# TurboMaster-clean.net
KiCad netlist of a schematic drawn in EAGLE
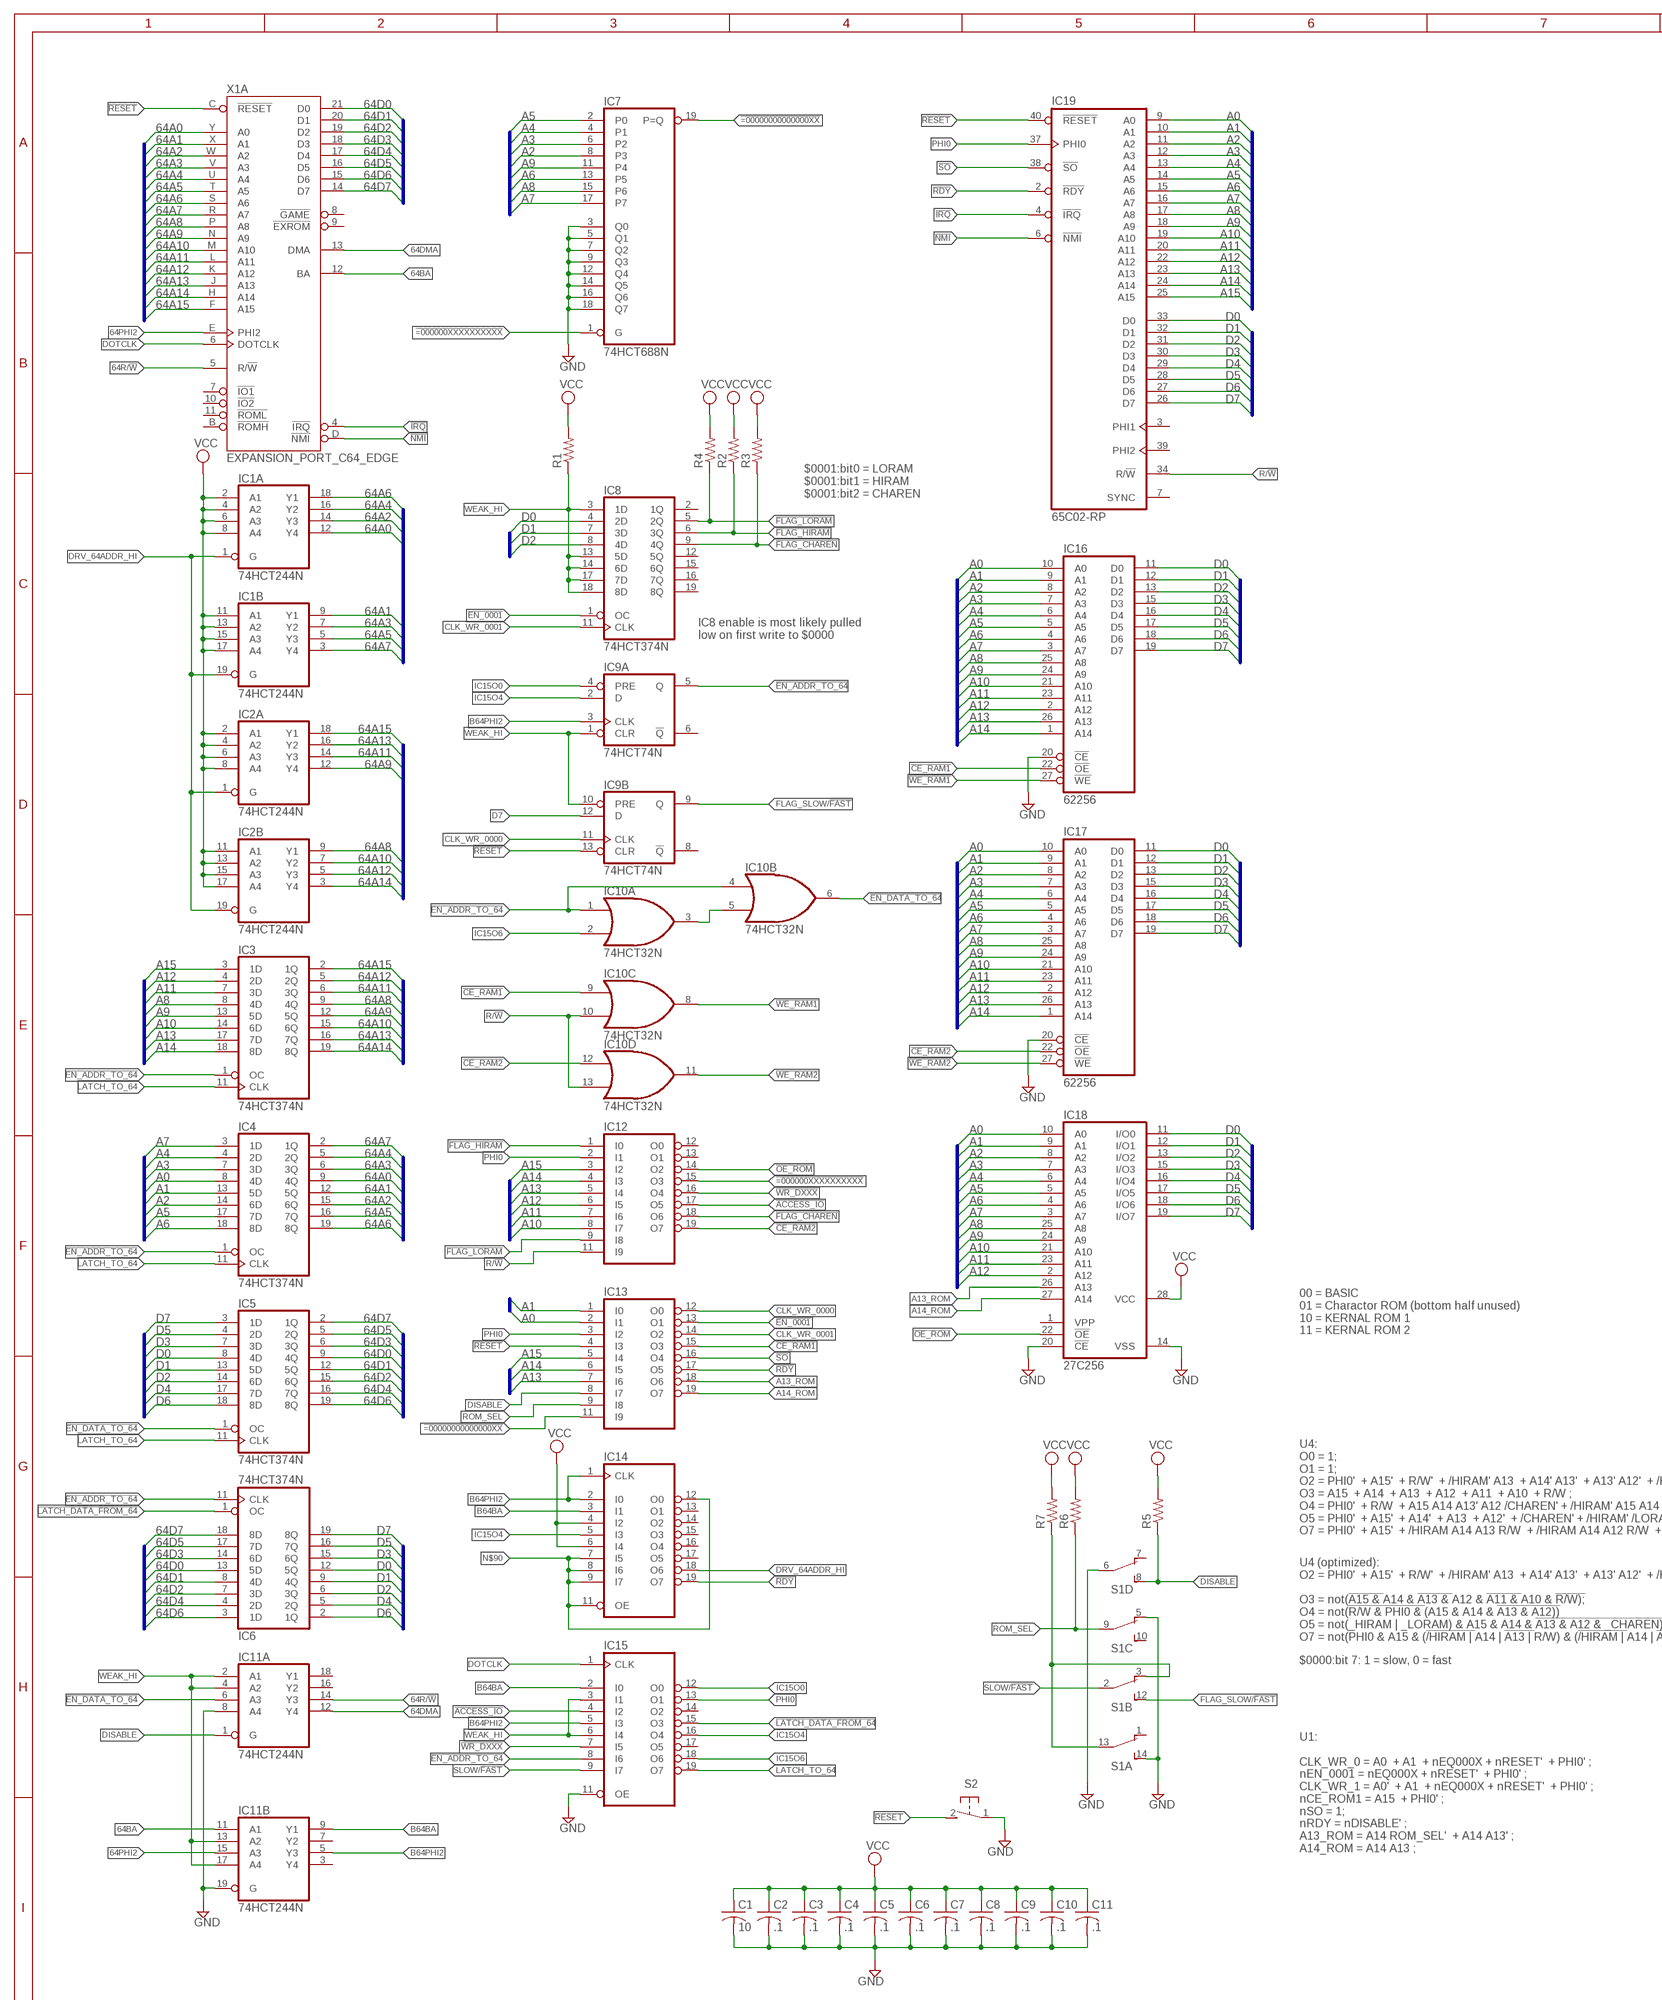
[diagram p0: schematic, sheet 1, part 1 of 2]
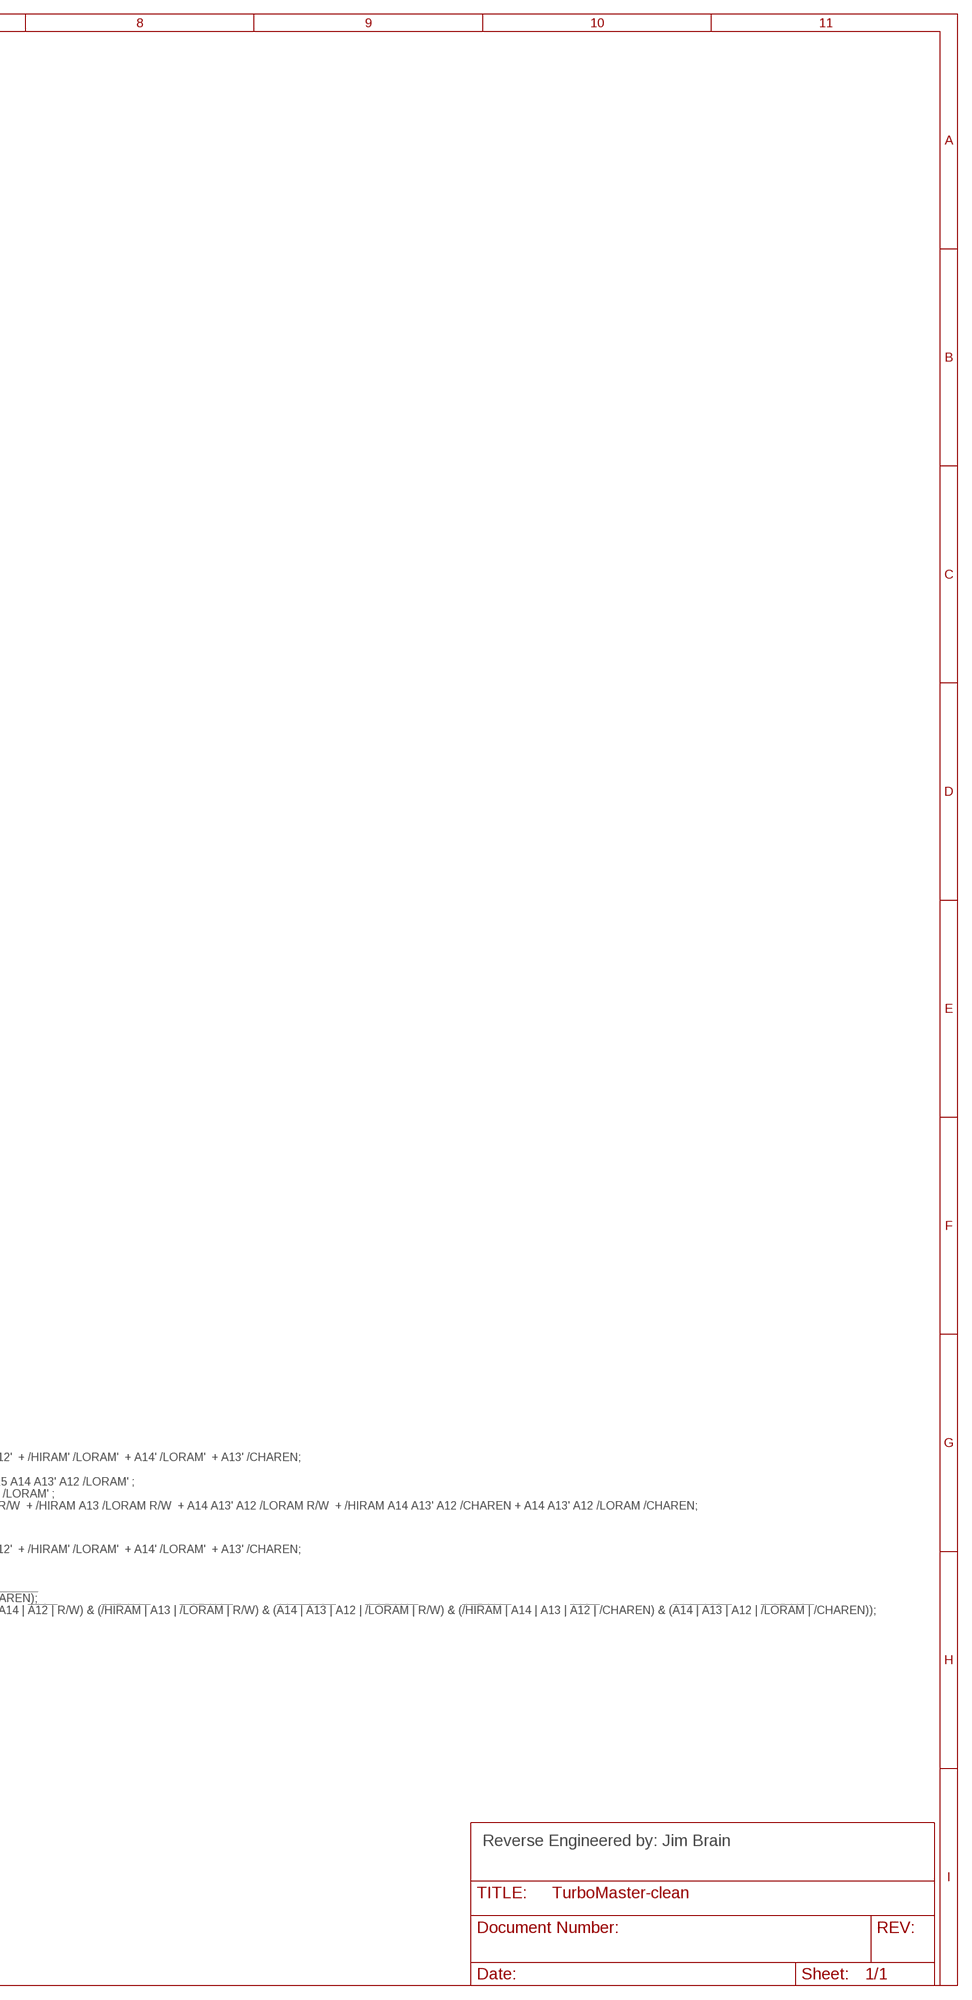
[diagram p1: schematic, sheet 1, part 2 of 2]

(export (version "E")
  (design (tool "Eeschema 10.0.6"))
  (components
    (comp (ref "C1")
      (value "10")
      (footprint "eagle-import:C050-024X044")
      (libsource (lib "eagle-import") (part "C-US050-024X044"))
    )
    (comp (ref "C2")
      (value ".1")
      (footprint "eagle-import:C050-024X044")
      (libsource (lib "eagle-import") (part "C-US050-024X044"))
    )
    (comp (ref "C3")
      (value ".1")
      (footprint "eagle-import:C050-024X044")
      (libsource (lib "eagle-import") (part "C-US050-024X044"))
    )
    (comp (ref "C4")
      (value ".1")
      (footprint "eagle-import:C050-024X044")
      (libsource (lib "eagle-import") (part "C-US050-024X044"))
    )
    (comp (ref "C5")
      (value ".1")
      (footprint "eagle-import:C050-024X044")
      (libsource (lib "eagle-import") (part "C-US050-024X044"))
    )
    (comp (ref "C6")
      (value ".1")
      (footprint "eagle-import:C050-024X044")
      (libsource (lib "eagle-import") (part "C-US050-024X044"))
    )
    (comp (ref "C7")
      (value ".1")
      (footprint "eagle-import:C050-024X044")
      (libsource (lib "eagle-import") (part "C-US050-024X044"))
    )
    (comp (ref "C8")
      (value ".1")
      (footprint "eagle-import:C050-024X044")
      (libsource (lib "eagle-import") (part "C-US050-024X044"))
    )
    (comp (ref "C9")
      (value ".1")
      (footprint "eagle-import:C050-024X044")
      (libsource (lib "eagle-import") (part "C-US050-024X044"))
    )
    (comp (ref "C10")
      (value ".1")
      (footprint "eagle-import:C050-024X044")
      (libsource (lib "eagle-import") (part "C-US050-024X044"))
    )
    (comp (ref "C11")
      (value ".1")
      (footprint "eagle-import:C050-024X044")
      (libsource (lib "eagle-import") (part "C-US050-024X044"))
    )
    (comp (ref "IC1")
      (value "74HCT244N")
      (footprint "eagle-import:DIL20-RP")
      (libsource (lib "eagle-import") (part "74244NHCT"))
    )
    (comp (ref "IC2")
      (value "74HCT244N")
      (footprint "eagle-import:DIL20-RP")
      (libsource (lib "eagle-import") (part "74244NHCT"))
    )
    (comp (ref "IC3")
      (value "74HCT374N")
      (footprint "eagle-import:DIL20-RP")
      (libsource (lib "eagle-import") (part "74374NHCT"))
    )
    (comp (ref "IC4")
      (value "74HCT374N")
      (footprint "eagle-import:DIL20-RP")
      (libsource (lib "eagle-import") (part "74374NHCT"))
    )
    (comp (ref "IC5")
      (value "74HCT374N")
      (footprint "eagle-import:DIL20-RP")
      (libsource (lib "eagle-import") (part "74374NHCT"))
    )
    (comp (ref "IC6")
      (value "74HCT374N")
      (footprint "eagle-import:DIL20-RP")
      (libsource (lib "eagle-import") (part "74374NHCT"))
    )
    (comp (ref "IC7")
      (value "74HCT688N")
      (footprint "eagle-import:DIL20-RP")
      (libsource (lib "eagle-import") (part "74688NHCT"))
    )
    (comp (ref "IC8")
      (value "74HCT374N")
      (footprint "eagle-import:DIL20-RP")
      (libsource (lib "eagle-import") (part "74374NHCT"))
    )
    (comp (ref "IC9")
      (value "74HCT74N")
      (footprint "eagle-import:DIL14-RP")
      (libsource (lib "eagle-import") (part "7474NHCT"))
    )
    (comp (ref "IC10")
      (value "74HCT32N")
      (footprint "eagle-import:DIL14-RP")
      (libsource (lib "eagle-import") (part "7432NHCT"))
    )
    (comp (ref "IC11")
      (value "74HCT244N")
      (footprint "eagle-import:DIL20-RP")
      (libsource (lib "eagle-import") (part "74244NHCT"))
    )
    (comp (ref "IC12")
      (value "16L8-RP")
      (footprint "eagle-import:DIL20-RP")
      (libsource (lib "eagle-import") (part "16L8-RP"))
    )
    (comp (ref "IC13")
      (value "16L8-RP")
      (footprint "eagle-import:DIL20-RP")
      (libsource (lib "eagle-import") (part "16L8-RP"))
    )
    (comp (ref "IC14")
      (value "16R4-RP")
      (footprint "eagle-import:DIL20-RP")
      (libsource (lib "eagle-import") (part "16R4-RP"))
    )
    (comp (ref "IC15")
      (value "16R6-RP")
      (footprint "eagle-import:DIL20-RP")
      (libsource (lib "eagle-import") (part "16R6-RP"))
    )
    (comp (ref "IC16")
      (value "62256")
      (footprint "eagle-import:DIL28-6-RP")
      (libsource (lib "eagle-import") (part "JEDEC_32KB_SRAM-RP"))
    )
    (comp (ref "IC17")
      (value "62256")
      (footprint "eagle-import:DIL28-6-RP")
      (libsource (lib "eagle-import") (part "JEDEC_32KB_SRAM-RP"))
    )
    (comp (ref "IC18")
      (value "27C256")
      (footprint "eagle-import:DIL28-6-RP")
      (libsource (lib "eagle-import") (part "27C256AG-RP"))
    )
    (comp (ref "IC19")
      (value "65C02-RP")
      (footprint "eagle-import:DIL40-ROUNDPAD")
      (libsource (lib "eagle-import") (part "6502-RPC"))
    )
    (comp (ref "R1")
      (value "R-US_0207/10")
      (footprint "eagle-import:0207_10")
      (libsource (lib "eagle-import") (part "R-US_0207/10"))
    )
    (comp (ref "R2")
      (value "R-US_0207/10")
      (footprint "eagle-import:0207_10")
      (libsource (lib "eagle-import") (part "R-US_0207/10"))
    )
    (comp (ref "R3")
      (value "R-US_0207/10")
      (footprint "eagle-import:0207_10")
      (libsource (lib "eagle-import") (part "R-US_0207/10"))
    )
    (comp (ref "R4")
      (value "R-US_0207/10")
      (footprint "eagle-import:0207_10")
      (libsource (lib "eagle-import") (part "R-US_0207/10"))
    )
    (comp (ref "R5")
      (value "R-US_0207/10")
      (footprint "eagle-import:0207_10")
      (libsource (lib "eagle-import") (part "R-US_0207/10"))
    )
    (comp (ref "R6")
      (value "R-US_0207/10")
      (footprint "eagle-import:0207_10")
      (libsource (lib "eagle-import") (part "R-US_0207/10"))
    )
    (comp (ref "R7")
      (value "R-US_0207/10")
      (footprint "eagle-import:0207_10")
      (libsource (lib "eagle-import") (part "R-US_0207/10"))
    )
    (comp (ref "S1")
      (value "DIP04DPDTS-RP")
      (footprint "eagle-import:DIP04DPDTS-RP")
      (libsource (lib "eagle-import") (part "DIP04DPDTS-RP"))
    )
    (comp (ref "S2")
      (value "31-XX")
      (footprint "eagle-import:B3F-31XX")
      (fields (field (name "MPN") "B3F-3100"))
      (libsource (lib "eagle-import") (part "31-XX"))
    )
    (comp (ref "X1")
      (value "EXPANSION_PORT_C64_EDGE")
      (footprint "eagle-import:MA100-22-2")
      (libsource (lib "eagle-import") (part "EXPANSION_PORT_C64_EDGE"))
    )
  )
  (nets
    (net (code "1") (name "/64A0") (class "Default")
      (node (ref "IC1") (pin "12") (pinfunction "Y4_12") (pintype "tri_state"))
      (node (ref "IC4") (pin "9") (pinfunction "4Q_9") (pintype "tri_state"))
      (node (ref "X1") (pin "Y") (pinfunction "A0_Y") (pintype "bidirectional"))
    )
    (net (code "2") (name "/64A1") (class "Default")
      (node (ref "IC1") (pin "9") (pinfunction "Y1_9") (pintype "tri_state"))
      (node (ref "IC4") (pin "12") (pinfunction "5Q_12") (pintype "tri_state"))
      (node (ref "X1") (pin "X") (pinfunction "A1_X") (pintype "bidirectional"))
    )
    (net (code "3") (name "/64A2") (class "Default")
      (node (ref "IC1") (pin "14") (pinfunction "Y3_14") (pintype "tri_state"))
      (node (ref "IC4") (pin "15") (pinfunction "6Q_15") (pintype "tri_state"))
      (node (ref "X1") (pin "W") (pinfunction "A2_W") (pintype "bidirectional"))
    )
    (net (code "4") (name "/64A3") (class "Default")
      (node (ref "IC1") (pin "7") (pinfunction "Y2_7") (pintype "tri_state"))
      (node (ref "IC4") (pin "6") (pinfunction "3Q_6") (pintype "tri_state"))
      (node (ref "X1") (pin "V") (pinfunction "A3_V") (pintype "bidirectional"))
    )
    (net (code "5") (name "/64A4") (class "Default")
      (node (ref "IC1") (pin "16") (pinfunction "Y2_16") (pintype "tri_state"))
      (node (ref "IC4") (pin "5") (pinfunction "2Q_5") (pintype "tri_state"))
      (node (ref "X1") (pin "U") (pinfunction "A4_U") (pintype "bidirectional"))
    )
    (net (code "6") (name "/64A5") (class "Default")
      (node (ref "IC1") (pin "5") (pinfunction "Y3_5") (pintype "tri_state"))
      (node (ref "IC4") (pin "16") (pinfunction "7Q_16") (pintype "tri_state"))
      (node (ref "X1") (pin "T") (pinfunction "A5_T") (pintype "bidirectional"))
    )
    (net (code "7") (name "/64A6") (class "Default")
      (node (ref "IC1") (pin "18") (pinfunction "Y1_18") (pintype "tri_state"))
      (node (ref "IC4") (pin "19") (pinfunction "8Q_19") (pintype "tri_state"))
      (node (ref "X1") (pin "S") (pinfunction "A6_S") (pintype "bidirectional"))
    )
    (net (code "8") (name "/64A7") (class "Default")
      (node (ref "IC1") (pin "3") (pinfunction "Y4_3") (pintype "tri_state"))
      (node (ref "IC4") (pin "2") (pinfunction "1Q_2") (pintype "tri_state"))
      (node (ref "X1") (pin "R") (pinfunction "A7_R") (pintype "bidirectional"))
    )
    (net (code "9") (name "/64A8") (class "Default")
      (node (ref "IC2") (pin "9") (pinfunction "Y1_9") (pintype "tri_state"))
      (node (ref "IC3") (pin "9") (pinfunction "4Q_9") (pintype "tri_state"))
      (node (ref "X1") (pin "P") (pinfunction "A8_P") (pintype "bidirectional"))
    )
    (net (code "10") (name "/64A9") (class "Default")
      (node (ref "IC2") (pin "12") (pinfunction "Y4_12") (pintype "tri_state"))
      (node (ref "IC3") (pin "12") (pinfunction "5Q_12") (pintype "tri_state"))
      (node (ref "X1") (pin "N") (pinfunction "A9_N") (pintype "bidirectional"))
    )
    (net (code "11") (name "/64A10") (class "Default")
      (node (ref "IC2") (pin "7") (pinfunction "Y2_7") (pintype "tri_state"))
      (node (ref "IC3") (pin "15") (pinfunction "6Q_15") (pintype "tri_state"))
      (node (ref "X1") (pin "M") (pinfunction "A10_M") (pintype "bidirectional"))
    )
    (net (code "12") (name "/64A11") (class "Default")
      (node (ref "IC2") (pin "14") (pinfunction "Y3_14") (pintype "tri_state"))
      (node (ref "IC3") (pin "6") (pinfunction "3Q_6") (pintype "tri_state"))
      (node (ref "X1") (pin "L") (pinfunction "A11_L") (pintype "bidirectional"))
    )
    (net (code "13") (name "/64A12") (class "Default")
      (node (ref "IC2") (pin "5") (pinfunction "Y3_5") (pintype "tri_state"))
      (node (ref "IC3") (pin "5") (pinfunction "2Q_5") (pintype "tri_state"))
      (node (ref "X1") (pin "K") (pinfunction "A12_K") (pintype "bidirectional"))
    )
    (net (code "14") (name "/64A13") (class "Default")
      (node (ref "IC2") (pin "16") (pinfunction "Y2_16") (pintype "tri_state"))
      (node (ref "IC3") (pin "16") (pinfunction "7Q_16") (pintype "tri_state"))
      (node (ref "X1") (pin "J") (pinfunction "A13_J") (pintype "bidirectional"))
    )
    (net (code "15") (name "/64A14") (class "Default")
      (node (ref "IC2") (pin "3") (pinfunction "Y4_3") (pintype "tri_state"))
      (node (ref "IC3") (pin "19") (pinfunction "8Q_19") (pintype "tri_state"))
      (node (ref "X1") (pin "H") (pinfunction "A14_H") (pintype "bidirectional"))
    )
    (net (code "16") (name "/64A15") (class "Default")
      (node (ref "IC2") (pin "18") (pinfunction "Y1_18") (pintype "tri_state"))
      (node (ref "IC3") (pin "2") (pinfunction "1Q_2") (pintype "tri_state"))
      (node (ref "X1") (pin "F") (pinfunction "A15_F") (pintype "bidirectional"))
    )
    (net (code "17") (name "/64D0") (class "Default")
      (node (ref "IC5") (pin "9") (pinfunction "4Q_9") (pintype "tri_state"))
      (node (ref "IC6") (pin "13") (pinfunction "5D_13") (pintype "input"))
      (node (ref "X1") (pin "21") (pinfunction "D0_21") (pintype "bidirectional"))
    )
    (net (code "18") (name "/64D1") (class "Default")
      (node (ref "IC5") (pin "12") (pinfunction "5Q_12") (pintype "tri_state"))
      (node (ref "IC6") (pin "8") (pinfunction "4D_8") (pintype "input"))
      (node (ref "X1") (pin "20") (pinfunction "D1_20") (pintype "bidirectional"))
    )
    (net (code "19") (name "/64D2") (class "Default")
      (node (ref "IC5") (pin "15") (pinfunction "6Q_15") (pintype "tri_state"))
      (node (ref "IC6") (pin "7") (pinfunction "3D_7") (pintype "input"))
      (node (ref "X1") (pin "19") (pinfunction "D2_19") (pintype "bidirectional"))
    )
    (net (code "20") (name "/64D3") (class "Default")
      (node (ref "IC5") (pin "6") (pinfunction "3Q_6") (pintype "tri_state"))
      (node (ref "IC6") (pin "14") (pinfunction "6D_14") (pintype "input"))
      (node (ref "X1") (pin "18") (pinfunction "D3_18") (pintype "bidirectional"))
    )
    (net (code "21") (name "/64D4") (class "Default")
      (node (ref "IC5") (pin "16") (pinfunction "7Q_16") (pintype "tri_state"))
      (node (ref "IC6") (pin "4") (pinfunction "2D_4") (pintype "input"))
      (node (ref "X1") (pin "17") (pinfunction "D4_17") (pintype "bidirectional"))
    )
    (net (code "22") (name "/64D5") (class "Default")
      (node (ref "IC5") (pin "5") (pinfunction "2Q_5") (pintype "tri_state"))
      (node (ref "IC6") (pin "17") (pinfunction "7D_17") (pintype "input"))
      (node (ref "X1") (pin "16") (pinfunction "D5_16") (pintype "bidirectional"))
    )
    (net (code "23") (name "/64D6") (class "Default")
      (node (ref "IC5") (pin "19") (pinfunction "8Q_19") (pintype "tri_state"))
      (node (ref "IC6") (pin "3") (pinfunction "1D_3") (pintype "input"))
      (node (ref "X1") (pin "15") (pinfunction "D6_15") (pintype "bidirectional"))
    )
    (net (code "24") (name "/64D7") (class "Default")
      (node (ref "IC5") (pin "2") (pinfunction "1Q_2") (pintype "tri_state"))
      (node (ref "IC6") (pin "18") (pinfunction "8D_18") (pintype "input"))
      (node (ref "X1") (pin "14") (pinfunction "D7_14") (pintype "bidirectional"))
    )
    (net (code "25") (name "/64R{slash}~{W}") (class "Default")
      (node (ref "IC11") (pin "14") (pinfunction "Y3_14") (pintype "tri_state"))
      (node (ref "X1") (pin "5") (pinfunction "R/~{W}_5") (pintype "bidirectional"))
    )
    (net (code "26") (name "/A0") (class "Default")
      (node (ref "IC13") (pin "2") (pinfunction "I1_2") (pintype "input"))
      (node (ref "IC16") (pin "10") (pinfunction "A0_10") (pintype "input"))
      (node (ref "IC17") (pin "10") (pinfunction "A0_10") (pintype "input"))
      (node (ref "IC18") (pin "10") (pinfunction "A0_10") (pintype "input"))
      (node (ref "IC19") (pin "9") (pinfunction "A0_9") (pintype "output"))
      (node (ref "IC4") (pin "8") (pinfunction "4D_8") (pintype "input"))
    )
    (net (code "27") (name "/A1") (class "Default")
      (node (ref "IC13") (pin "1") (pinfunction "I0_1") (pintype "input"))
      (node (ref "IC16") (pin "9") (pinfunction "A1_9") (pintype "input"))
      (node (ref "IC17") (pin "9") (pinfunction "A1_9") (pintype "input"))
      (node (ref "IC18") (pin "9") (pinfunction "A1_9") (pintype "input"))
      (node (ref "IC19") (pin "10") (pinfunction "A1_10") (pintype "output"))
      (node (ref "IC4") (pin "13") (pinfunction "5D_13") (pintype "input"))
    )
    (net (code "28") (name "/A2") (class "Default")
      (node (ref "IC16") (pin "8") (pinfunction "A2_8") (pintype "input"))
      (node (ref "IC17") (pin "8") (pinfunction "A2_8") (pintype "input"))
      (node (ref "IC18") (pin "8") (pinfunction "A2_8") (pintype "input"))
      (node (ref "IC19") (pin "11") (pinfunction "A2_11") (pintype "output"))
      (node (ref "IC4") (pin "14") (pinfunction "6D_14") (pintype "input"))
      (node (ref "IC7") (pin "8") (pinfunction "P3_8") (pintype "input"))
    )
    (net (code "29") (name "/A3") (class "Default")
      (node (ref "IC16") (pin "7") (pinfunction "A3_7") (pintype "input"))
      (node (ref "IC17") (pin "7") (pinfunction "A3_7") (pintype "input"))
      (node (ref "IC18") (pin "7") (pinfunction "A3_7") (pintype "input"))
      (node (ref "IC19") (pin "12") (pinfunction "A3_12") (pintype "output"))
      (node (ref "IC4") (pin "7") (pinfunction "3D_7") (pintype "input"))
      (node (ref "IC7") (pin "6") (pinfunction "P2_6") (pintype "input"))
    )
    (net (code "30") (name "/A4") (class "Default")
      (node (ref "IC16") (pin "6") (pinfunction "A4_6") (pintype "input"))
      (node (ref "IC17") (pin "6") (pinfunction "A4_6") (pintype "input"))
      (node (ref "IC18") (pin "6") (pinfunction "A4_6") (pintype "input"))
      (node (ref "IC19") (pin "13") (pinfunction "A4_13") (pintype "output"))
      (node (ref "IC4") (pin "4") (pinfunction "2D_4") (pintype "input"))
      (node (ref "IC7") (pin "4") (pinfunction "P1_4") (pintype "input"))
    )
    (net (code "31") (name "/A5") (class "Default")
      (node (ref "IC16") (pin "5") (pinfunction "A5_5") (pintype "input"))
      (node (ref "IC17") (pin "5") (pinfunction "A5_5") (pintype "input"))
      (node (ref "IC18") (pin "5") (pinfunction "A5_5") (pintype "input"))
      (node (ref "IC19") (pin "14") (pinfunction "A5_14") (pintype "output"))
      (node (ref "IC4") (pin "17") (pinfunction "7D_17") (pintype "input"))
      (node (ref "IC7") (pin "2") (pinfunction "P0_2") (pintype "input"))
    )
    (net (code "32") (name "/A6") (class "Default")
      (node (ref "IC16") (pin "4") (pinfunction "A6_4") (pintype "input"))
      (node (ref "IC17") (pin "4") (pinfunction "A6_4") (pintype "input"))
      (node (ref "IC18") (pin "4") (pinfunction "A6_4") (pintype "input"))
      (node (ref "IC19") (pin "15") (pinfunction "A6_15") (pintype "output"))
      (node (ref "IC4") (pin "18") (pinfunction "8D_18") (pintype "input"))
      (node (ref "IC7") (pin "13") (pinfunction "P5_13") (pintype "input"))
    )
    (net (code "33") (name "/A7") (class "Default")
      (node (ref "IC16") (pin "3") (pinfunction "A7_3") (pintype "input"))
      (node (ref "IC17") (pin "3") (pinfunction "A7_3") (pintype "input"))
      (node (ref "IC18") (pin "3") (pinfunction "A7_3") (pintype "input"))
      (node (ref "IC19") (pin "16") (pinfunction "A7_16") (pintype "output"))
      (node (ref "IC4") (pin "3") (pinfunction "1D_3") (pintype "input"))
      (node (ref "IC7") (pin "17") (pinfunction "P7_17") (pintype "input"))
    )
    (net (code "34") (name "/A8") (class "Default")
      (node (ref "IC16") (pin "25") (pinfunction "A8_25") (pintype "input"))
      (node (ref "IC17") (pin "25") (pinfunction "A8_25") (pintype "input"))
      (node (ref "IC18") (pin "25") (pinfunction "A8_25") (pintype "input"))
      (node (ref "IC19") (pin "17") (pinfunction "A8_17") (pintype "output"))
      (node (ref "IC3") (pin "8") (pinfunction "4D_8") (pintype "input"))
      (node (ref "IC7") (pin "15") (pinfunction "P6_15") (pintype "input"))
    )
    (net (code "35") (name "/A9") (class "Default")
      (node (ref "IC16") (pin "24") (pinfunction "A9_24") (pintype "input"))
      (node (ref "IC17") (pin "24") (pinfunction "A9_24") (pintype "input"))
      (node (ref "IC18") (pin "24") (pinfunction "A9_24") (pintype "input"))
      (node (ref "IC19") (pin "18") (pinfunction "A9_18") (pintype "output"))
      (node (ref "IC3") (pin "13") (pinfunction "5D_13") (pintype "input"))
      (node (ref "IC7") (pin "11") (pinfunction "P4_11") (pintype "input"))
    )
    (net (code "36") (name "/A10") (class "Default")
      (node (ref "IC12") (pin "8") (pinfunction "I7_8") (pintype "input"))
      (node (ref "IC16") (pin "21") (pinfunction "A10_21") (pintype "input"))
      (node (ref "IC17") (pin "21") (pinfunction "A10_21") (pintype "input"))
      (node (ref "IC18") (pin "21") (pinfunction "A10_21") (pintype "input"))
      (node (ref "IC19") (pin "19") (pinfunction "A10_19") (pintype "output"))
      (node (ref "IC3") (pin "14") (pinfunction "6D_14") (pintype "input"))
    )
    (net (code "37") (name "/A11") (class "Default")
      (node (ref "IC12") (pin "7") (pinfunction "I6_7") (pintype "input"))
      (node (ref "IC16") (pin "23") (pinfunction "A11_23") (pintype "input"))
      (node (ref "IC17") (pin "23") (pinfunction "A11_23") (pintype "input"))
      (node (ref "IC18") (pin "23") (pinfunction "A11_23") (pintype "input"))
      (node (ref "IC19") (pin "20") (pinfunction "A11_20") (pintype "output"))
      (node (ref "IC3") (pin "7") (pinfunction "3D_7") (pintype "input"))
    )
    (net (code "38") (name "/A12") (class "Default")
      (node (ref "IC12") (pin "6") (pinfunction "I5_6") (pintype "input"))
      (node (ref "IC16") (pin "2") (pinfunction "A12_2") (pintype "input"))
      (node (ref "IC17") (pin "2") (pinfunction "A12_2") (pintype "input"))
      (node (ref "IC18") (pin "2") (pinfunction "A12_2") (pintype "input"))
      (node (ref "IC19") (pin "22") (pinfunction "A12_22") (pintype "output"))
      (node (ref "IC3") (pin "4") (pinfunction "2D_4") (pintype "input"))
    )
    (net (code "39") (name "/A13") (class "Default")
      (node (ref "IC12") (pin "5") (pinfunction "I4_5") (pintype "input"))
      (node (ref "IC13") (pin "7") (pinfunction "I6_7") (pintype "input"))
      (node (ref "IC16") (pin "26") (pinfunction "A13_26") (pintype "input"))
      (node (ref "IC17") (pin "26") (pinfunction "A13_26") (pintype "input"))
      (node (ref "IC19") (pin "23") (pinfunction "A13_23") (pintype "output"))
      (node (ref "IC3") (pin "17") (pinfunction "7D_17") (pintype "input"))
    )
    (net (code "40") (name "/A14") (class "Default")
      (node (ref "IC12") (pin "4") (pinfunction "I3_4") (pintype "input"))
      (node (ref "IC13") (pin "6") (pinfunction "I5_6") (pintype "input"))
      (node (ref "IC16") (pin "1") (pinfunction "A14_1") (pintype "input"))
      (node (ref "IC17") (pin "1") (pinfunction "A14_1") (pintype "input"))
      (node (ref "IC19") (pin "24") (pinfunction "A14_24") (pintype "output"))
      (node (ref "IC3") (pin "18") (pinfunction "8D_18") (pintype "input"))
    )
    (net (code "41") (name "/A15") (class "Default")
      (node (ref "IC12") (pin "3") (pinfunction "I2_3") (pintype "input"))
      (node (ref "IC13") (pin "5") (pinfunction "I4_5") (pintype "input"))
      (node (ref "IC19") (pin "25") (pinfunction "A15_25") (pintype "output"))
      (node (ref "IC3") (pin "3") (pinfunction "1D_3") (pintype "input"))
    )
    (net (code "42") (name "/D0") (class "Default")
      (node (ref "IC16") (pin "11") (pinfunction "D0_11") (pintype "bidirectional"))
      (node (ref "IC17") (pin "11") (pinfunction "D0_11") (pintype "bidirectional"))
      (node (ref "IC18") (pin "11") (pinfunction "I/O0_11") (pintype "tri_state"))
      (node (ref "IC19") (pin "33") (pinfunction "D0_33") (pintype "bidirectional"))
      (node (ref "IC5") (pin "8") (pinfunction "4D_8") (pintype "input"))
      (node (ref "IC6") (pin "12") (pinfunction "5Q_12") (pintype "tri_state"))
      (node (ref "IC8") (pin "4") (pinfunction "2D_4") (pintype "input"))
    )
    (net (code "43") (name "/D1") (class "Default")
      (node (ref "IC16") (pin "12") (pinfunction "D1_12") (pintype "bidirectional"))
      (node (ref "IC17") (pin "12") (pinfunction "D1_12") (pintype "bidirectional"))
      (node (ref "IC18") (pin "12") (pinfunction "I/O1_12") (pintype "tri_state"))
      (node (ref "IC19") (pin "32") (pinfunction "D1_32") (pintype "bidirectional"))
      (node (ref "IC5") (pin "13") (pinfunction "5D_13") (pintype "input"))
      (node (ref "IC6") (pin "9") (pinfunction "4Q_9") (pintype "tri_state"))
      (node (ref "IC8") (pin "7") (pinfunction "3D_7") (pintype "input"))
    )
    (net (code "44") (name "/D2") (class "Default")
      (node (ref "IC16") (pin "13") (pinfunction "D2_13") (pintype "bidirectional"))
      (node (ref "IC17") (pin "13") (pinfunction "D2_13") (pintype "bidirectional"))
      (node (ref "IC18") (pin "13") (pinfunction "I/O2_13") (pintype "tri_state"))
      (node (ref "IC19") (pin "31") (pinfunction "D2_31") (pintype "bidirectional"))
      (node (ref "IC5") (pin "14") (pinfunction "6D_14") (pintype "input"))
      (node (ref "IC6") (pin "6") (pinfunction "3Q_6") (pintype "tri_state"))
      (node (ref "IC8") (pin "8") (pinfunction "4D_8") (pintype "input"))
    )
    (net (code "45") (name "/D3") (class "Default")
      (node (ref "IC16") (pin "15") (pinfunction "D3_15") (pintype "bidirectional"))
      (node (ref "IC17") (pin "15") (pinfunction "D3_15") (pintype "bidirectional"))
      (node (ref "IC18") (pin "15") (pinfunction "I/O3_15") (pintype "tri_state"))
      (node (ref "IC19") (pin "30") (pinfunction "D3_30") (pintype "bidirectional"))
      (node (ref "IC5") (pin "7") (pinfunction "3D_7") (pintype "input"))
      (node (ref "IC6") (pin "15") (pinfunction "6Q_15") (pintype "tri_state"))
    )
    (net (code "46") (name "/D4") (class "Default")
      (node (ref "IC16") (pin "16") (pinfunction "D4_16") (pintype "bidirectional"))
      (node (ref "IC17") (pin "16") (pinfunction "D4_16") (pintype "bidirectional"))
      (node (ref "IC18") (pin "16") (pinfunction "I/O4_16") (pintype "tri_state"))
      (node (ref "IC19") (pin "29") (pinfunction "D4_29") (pintype "bidirectional"))
      (node (ref "IC5") (pin "17") (pinfunction "7D_17") (pintype "input"))
      (node (ref "IC6") (pin "5") (pinfunction "2Q_5") (pintype "tri_state"))
    )
    (net (code "47") (name "/D5") (class "Default")
      (node (ref "IC16") (pin "17") (pinfunction "D5_17") (pintype "bidirectional"))
      (node (ref "IC17") (pin "17") (pinfunction "D5_17") (pintype "bidirectional"))
      (node (ref "IC18") (pin "17") (pinfunction "I/O5_17") (pintype "tri_state"))
      (node (ref "IC19") (pin "28") (pinfunction "D5_28") (pintype "bidirectional"))
      (node (ref "IC5") (pin "4") (pinfunction "2D_4") (pintype "input"))
      (node (ref "IC6") (pin "16") (pinfunction "7Q_16") (pintype "tri_state"))
    )
    (net (code "48") (name "/D6") (class "Default")
      (node (ref "IC16") (pin "18") (pinfunction "D6_18") (pintype "bidirectional"))
      (node (ref "IC17") (pin "18") (pinfunction "D6_18") (pintype "bidirectional"))
      (node (ref "IC18") (pin "18") (pinfunction "I/O6_18") (pintype "tri_state"))
      (node (ref "IC19") (pin "27") (pinfunction "D6_27") (pintype "bidirectional"))
      (node (ref "IC5") (pin "18") (pinfunction "8D_18") (pintype "input"))
      (node (ref "IC6") (pin "2") (pinfunction "1Q_2") (pintype "tri_state"))
    )
    (net (code "49") (name "/FLAG_SLOW{slash}~{FAST}") (class "Default")
      (node (ref "IC9") (pin "9") (pinfunction "Q_9") (pintype "output"))
      (node (ref "S1") (pin "12") (pinfunction "S_12") (pintype "passive"))
    )
    (net (code "50") (name "/R{slash}~{W}") (class "Default")
      (node (ref "IC10") (pin "10") (pinfunction "I1_10") (pintype "input"))
      (node (ref "IC10") (pin "13") (pinfunction "I1_13") (pintype "input"))
      (node (ref "IC12") (pin "11") (pinfunction "I9_11") (pintype "input"))
      (node (ref "IC19") (pin "34") (pinfunction "R/~{W}_34") (pintype "output"))
    )
    (net (code "51") (name "/SLOW{slash}~{FAST}") (class "Default")
      (node (ref "IC15") (pin "9") (pinfunction "I7_9") (pintype "input"))
      (node (ref "S1") (pin "2") (pinfunction "P_2") (pintype "passive"))
    )
    (net (code "52") (name "/~{=000000XXXXXXXXXX}") (class "Default")
      (node (ref "IC12") (pin "15") (pinfunction "O3_15") (pintype "bidirectional"))
      (node (ref "IC7") (pin "1") (pinfunction "G_1") (pintype "input"))
    )
    (net (code "53") (name "/~{=00000000000000XX}") (class "Default")
      (node (ref "IC13") (pin "11") (pinfunction "I9_11") (pintype "input"))
      (node (ref "IC7") (pin "19") (pinfunction "P=Q_19") (pintype "output"))
    )
    (net (code "54") (name "/~{ACCESS_IO}") (class "Default")
      (node (ref "IC12") (pin "17") (pinfunction "O5_17") (pintype "bidirectional"))
      (node (ref "IC15") (pin "4") (pinfunction "I2_4") (pintype "input"))
    )
    (net (code "55") (name "/~{CE_RAM1}") (class "Default")
      (node (ref "IC10") (pin "9") (pinfunction "I0_9") (pintype "input"))
      (node (ref "IC13") (pin "15") (pinfunction "O3_15") (pintype "bidirectional"))
      (node (ref "IC16") (pin "22") (pinfunction "~{OE}_22") (pintype "input"))
    )
    (net (code "56") (name "/~{CE_RAM2}") (class "Default")
      (node (ref "IC10") (pin "12") (pinfunction "I0_12") (pintype "input"))
      (node (ref "IC12") (pin "19") (pinfunction "O7_19") (pintype "output"))
      (node (ref "IC17") (pin "22") (pinfunction "~{OE}_22") (pintype "input"))
    )
    (net (code "57") (name "/~{EN_0001}") (class "Default")
      (node (ref "IC13") (pin "13") (pinfunction "O1_13") (pintype "bidirectional"))
      (node (ref "IC8") (pin "1") (pinfunction "OC_1") (pintype "input"))
    )
    (net (code "58") (name "/~{EN_ADDR_TO_64}") (class "Default")
      (node (ref "IC10") (pin "1") (pinfunction "I0_1") (pintype "input"))
      (node (ref "IC10") (pin "4") (pinfunction "I0_4") (pintype "input"))
      (node (ref "IC15") (pin "8") (pinfunction "I6_8") (pintype "input"))
      (node (ref "IC3") (pin "1") (pinfunction "OC_1") (pintype "input"))
      (node (ref "IC4") (pin "1") (pinfunction "OC_1") (pintype "input"))
      (node (ref "IC6") (pin "11") (pinfunction "CLK_11") (pintype "input"))
      (node (ref "IC9") (pin "5") (pinfunction "Q_5") (pintype "output"))
    )
    (net (code "59") (name "/~{EN_DATA_TO_64}") (class "Default")
      (node (ref "IC10") (pin "6") (pinfunction "O_6") (pintype "output"))
      (node (ref "IC11") (pin "6") (pinfunction "A3_6") (pintype "input"))
      (node (ref "IC5") (pin "1") (pinfunction "OC_1") (pintype "input"))
    )
    (net (code "60") (name "/~{FLAG_CHAREN}") (class "Default")
      (node (ref "IC12") (pin "18") (pinfunction "O6_18") (pintype "bidirectional"))
      (node (ref "IC8") (pin "9") (pinfunction "4Q_9") (pintype "tri_state"))
      (node (ref "R3") (pin "1") (pinfunction "1_1") (pintype "passive"))
    )
    (net (code "61") (name "/~{FLAG_HIRAM}") (class "Default")
      (node (ref "IC12") (pin "1") (pinfunction "I0_1") (pintype "input"))
      (node (ref "IC8") (pin "6") (pinfunction "3Q_6") (pintype "tri_state"))
      (node (ref "R2") (pin "1") (pinfunction "1_1") (pintype "passive"))
    )
    (net (code "62") (name "/~{FLAG_LORAM}") (class "Default")
      (node (ref "IC12") (pin "9") (pinfunction "I8_9") (pintype "input"))
      (node (ref "IC8") (pin "5") (pinfunction "2Q_5") (pintype "tri_state"))
      (node (ref "R4") (pin "1") (pinfunction "1_1") (pintype "passive"))
    )
    (net (code "63") (name "/~{IRQ}") (class "Default")
      (node (ref "IC19") (pin "4") (pinfunction "~{IRQ}_4") (pintype "input"))
      (node (ref "X1") (pin "4") (pinfunction "~{IRQ}_4") (pintype "open_collector"))
    )
    (net (code "64") (name "/~{LATCH_DATA_FROM_64}") (class "Default")
      (node (ref "IC15") (pin "15") (pinfunction "O3_15") (pintype "output"))
      (node (ref "IC6") (pin "1") (pinfunction "OC_1") (pintype "input"))
    )
    (net (code "65") (name "/~{NMI}") (class "Default")
      (node (ref "IC19") (pin "6") (pinfunction "~{NMI}_6") (pintype "input"))
      (node (ref "X1") (pin "D") (pinfunction "~{NMI}_D") (pintype "open_collector"))
    )
    (net (code "66") (name "/~{OE_ROM}") (class "Default")
      (node (ref "IC12") (pin "14") (pinfunction "O2_14") (pintype "bidirectional"))
      (node (ref "IC18") (pin "22") (pinfunction "~{OE}_22") (pintype "input"))
    )
    (net (code "67") (name "/~{RDY}") (class "Default")
      (node (ref "IC13") (pin "17") (pinfunction "O5_17") (pintype "bidirectional"))
      (node (ref "IC14") (pin "19") (pinfunction "O7_19") (pintype "bidirectional"))
      (node (ref "IC19") (pin "2") (pinfunction "~{RDY}_2") (pintype "input"))
    )
    (net (code "68") (name "/~{RESET}") (class "Default")
      (node (ref "IC13") (pin "4") (pinfunction "I3_4") (pintype "input"))
      (node (ref "IC19") (pin "40") (pinfunction "~{RESET}_40") (pintype "input"))
      (node (ref "IC9") (pin "13") (pinfunction "CLR_13") (pintype "input"))
      (node (ref "S2") (pin "2") (pinfunction "S_2") (pintype "passive"))
      (node (ref "X1") (pin "C") (pinfunction "~{RESET}_C") (pintype "open_collector"))
    )
    (net (code "69") (name "/~{SO}") (class "Default")
      (node (ref "IC13") (pin "16") (pinfunction "O4_16") (pintype "bidirectional"))
      (node (ref "IC19") (pin "38") (pinfunction "~{SO}_38") (pintype "input"))
    )
    (net (code "70") (name "/~{WE_RAM1}") (class "Default")
      (node (ref "IC10") (pin "8") (pinfunction "O_8") (pintype "output"))
      (node (ref "IC16") (pin "27") (pinfunction "~{WE}_27") (pintype "input"))
    )
    (net (code "71") (name "/~{WE_RAM2}") (class "Default")
      (node (ref "IC10") (pin "11") (pinfunction "O_11") (pintype "output"))
      (node (ref "IC17") (pin "27") (pinfunction "~{WE}_27") (pintype "input"))
    )
    (net (code "72") (name "/~{WR_DXXX}") (class "Default")
      (node (ref "IC12") (pin "16") (pinfunction "O4_16") (pintype "bidirectional"))
      (node (ref "IC15") (pin "7") (pinfunction "I5_7") (pintype "input"))
    )
    (net (code "73") (name "64BA") (class "Default")
      (node (ref "IC11") (pin "11") (pinfunction "A1_11") (pintype "input"))
      (node (ref "X1") (pin "12") (pinfunction "BA_12") (pintype "bidirectional"))
    )
    (net (code "74") (name "64DMA") (class "Default")
      (node (ref "IC11") (pin "12") (pinfunction "Y4_12") (pintype "tri_state"))
      (node (ref "X1") (pin "13") (pinfunction "DMA_13") (pintype "bidirectional"))
    )
    (net (code "75") (name "64PHI2") (class "Default")
      (node (ref "IC11") (pin "15") (pinfunction "A3_15") (pintype "input"))
      (node (ref "X1") (pin "E") (pinfunction "PHI2_E") (pintype "output"))
    )
    (net (code "76") (name "A13_ROM") (class "Default")
      (node (ref "IC13") (pin "18") (pinfunction "O6_18") (pintype "bidirectional"))
      (node (ref "IC18") (pin "26") (pinfunction "A13_26") (pintype "input"))
    )
    (net (code "77") (name "A14_ROM") (class "Default")
      (node (ref "IC13") (pin "19") (pinfunction "O7_19") (pintype "output"))
      (node (ref "IC18") (pin "27") (pinfunction "A14_27") (pintype "input"))
    )
    (net (code "78") (name "B64BA") (class "Default")
      (node (ref "IC11") (pin "9") (pinfunction "Y1_9") (pintype "tri_state"))
      (node (ref "IC14") (pin "3") (pinfunction "I1_3") (pintype "input"))
      (node (ref "IC15") (pin "2") (pinfunction "I0_2") (pintype "input"))
    )
    (net (code "79") (name "B64PHI2") (class "Default")
      (node (ref "IC11") (pin "5") (pinfunction "Y3_5") (pintype "tri_state"))
      (node (ref "IC14") (pin "1") (pinfunction "CLK_1") (pintype "input"))
      (node (ref "IC14") (pin "2") (pinfunction "I0_2") (pintype "input"))
      (node (ref "IC15") (pin "5") (pinfunction "I3_5") (pintype "input"))
      (node (ref "IC9") (pin "3") (pinfunction "CLK_3") (pintype "input"))
    )
    (net (code "80") (name "CLK_WR_0000") (class "Default")
      (node (ref "IC13") (pin "12") (pinfunction "O0_12") (pintype "output"))
      (node (ref "IC9") (pin "11") (pinfunction "CLK_11") (pintype "input"))
    )
    (net (code "81") (name "CLK_WR_0001") (class "Default")
      (node (ref "IC13") (pin "14") (pinfunction "O2_14") (pintype "bidirectional"))
      (node (ref "IC8") (pin "11") (pinfunction "CLK_11") (pintype "input"))
    )
    (net (code "82") (name "D7") (class "Default")
      (node (ref "IC16") (pin "19") (pinfunction "D7_19") (pintype "bidirectional"))
      (node (ref "IC17") (pin "19") (pinfunction "D7_19") (pintype "bidirectional"))
      (node (ref "IC18") (pin "19") (pinfunction "I/O7_19") (pintype "tri_state"))
      (node (ref "IC19") (pin "26") (pinfunction "D7_26") (pintype "bidirectional"))
      (node (ref "IC5") (pin "3") (pinfunction "1D_3") (pintype "input"))
      (node (ref "IC6") (pin "19") (pinfunction "8Q_19") (pintype "tri_state"))
      (node (ref "IC9") (pin "12") (pinfunction "D_12") (pintype "input"))
    )
    (net (code "83") (name "DISABLE") (class "Default")
      (node (ref "IC11") (pin "1") (pinfunction "G_1") (pintype "input"))
      (node (ref "IC13") (pin "8") (pinfunction "I7_8") (pintype "input"))
      (node (ref "R5") (pin "1") (pinfunction "1_1") (pintype "passive"))
      (node (ref "S1") (pin "8") (pinfunction "S_8") (pintype "passive"))
    )
    (net (code "84") (name "DOTCLK") (class "Default")
      (node (ref "IC15") (pin "1") (pinfunction "CLK_1") (pintype "input"))
      (node (ref "X1") (pin "6") (pinfunction "DOTCLK_6") (pintype "output"))
    )
    (net (code "85") (name "DRV_64ADDR_HI") (class "Default")
      (node (ref "IC1") (pin "1") (pinfunction "G_1") (pintype "input"))
      (node (ref "IC1") (pin "19") (pinfunction "G_19") (pintype "input"))
      (node (ref "IC14") (pin "18") (pinfunction "O6_18") (pintype "bidirectional"))
      (node (ref "IC2") (pin "1") (pinfunction "G_1") (pintype "input"))
      (node (ref "IC2") (pin "19") (pinfunction "G_19") (pintype "input"))
    )
    (net (code "86") (name "GND") (class "Default")
      (node (ref "C1") (pin "2") (pinfunction "2_2") (pintype "passive"))
      (node (ref "C10") (pin "2") (pinfunction "2_2") (pintype "passive"))
      (node (ref "C11") (pin "2") (pinfunction "2_2") (pintype "passive"))
      (node (ref "C2") (pin "2") (pinfunction "2_2") (pintype "passive"))
      (node (ref "C3") (pin "2") (pinfunction "2_2") (pintype "passive"))
      (node (ref "C4") (pin "2") (pinfunction "2_2") (pintype "passive"))
      (node (ref "C5") (pin "2") (pinfunction "2_2") (pintype "passive"))
      (node (ref "C6") (pin "2") (pinfunction "2_2") (pintype "passive"))
      (node (ref "C7") (pin "2") (pinfunction "2_2") (pintype "passive"))
      (node (ref "C8") (pin "2") (pinfunction "2_2") (pintype "passive"))
      (node (ref "C9") (pin "2") (pinfunction "2_2") (pintype "passive"))
      (node (ref "IC11") (pin "19") (pinfunction "G_19") (pintype "input"))
      (node (ref "IC11") (pin "8") (pinfunction "A4_8") (pintype "input"))
      (node (ref "IC15") (pin "11") (pinfunction "OE_11") (pintype "input"))
      (node (ref "IC16") (pin "20") (pinfunction "~{CE}_20") (pintype "input"))
      (node (ref "IC17") (pin "20") (pinfunction "~{CE}_20") (pintype "input"))
      (node (ref "IC18") (pin "14") (pinfunction "VSS_14") (pintype "power_in"))
      (node (ref "IC18") (pin "20") (pinfunction "~{CE}_20") (pintype "input"))
      (node (ref "IC7") (pin "12") (pinfunction "Q4_12") (pintype "input"))
      (node (ref "IC7") (pin "14") (pinfunction "Q5_14") (pintype "input"))
      (node (ref "IC7") (pin "16") (pinfunction "Q6_16") (pintype "input"))
      (node (ref "IC7") (pin "18") (pinfunction "Q7_18") (pintype "input"))
      (node (ref "IC7") (pin "3") (pinfunction "Q0_3") (pintype "input"))
      (node (ref "IC7") (pin "5") (pinfunction "Q1_5") (pintype "input"))
      (node (ref "IC7") (pin "7") (pinfunction "Q2_7") (pintype "input"))
      (node (ref "IC7") (pin "9") (pinfunction "Q3_9") (pintype "input"))
      (node (ref "S1") (pin "14") (pinfunction "S_14") (pintype "passive"))
      (node (ref "S1") (pin "5") (pinfunction "O_5") (pintype "passive"))
      (node (ref "S1") (pin "6") (pinfunction "P_6") (pintype "passive"))
      (node (ref "S2") (pin "1") (pinfunction "P_1") (pintype "passive"))
    )
    (net (code "87") (name "IC15O0") (class "Default")
      (node (ref "IC15") (pin "12") (pinfunction "O0_12") (pintype "bidirectional"))
      (node (ref "IC9") (pin "4") (pinfunction "PRE_4") (pintype "input"))
    )
    (net (code "88") (name "IC15O4") (class "Default")
      (node (ref "IC14") (pin "5") (pinfunction "I3_5") (pintype "input"))
      (node (ref "IC15") (pin "16") (pinfunction "O4_16") (pintype "output"))
      (node (ref "IC9") (pin "2") (pinfunction "D_2") (pintype "input"))
    )
    (net (code "89") (name "IC15O6") (class "Default")
      (node (ref "IC10") (pin "2") (pinfunction "I1_2") (pintype "input"))
      (node (ref "IC15") (pin "18") (pinfunction "O6_18") (pintype "output"))
    )
    (net (code "90") (name "LATCH_TO_64") (class "Default")
      (node (ref "IC15") (pin "19") (pinfunction "O7_19") (pintype "bidirectional"))
      (node (ref "IC3") (pin "11") (pinfunction "CLK_11") (pintype "input"))
      (node (ref "IC4") (pin "11") (pinfunction "CLK_11") (pintype "input"))
      (node (ref "IC5") (pin "11") (pinfunction "CLK_11") (pintype "input"))
    )
    (net (code "91") (name "N$90") (class "Default")
      (node (ref "IC14") (pin "11") (pinfunction "OE_11") (pintype "input"))
      (node (ref "IC14") (pin "12") (pinfunction "O0_12") (pintype "bidirectional"))
      (node (ref "IC14") (pin "7") (pinfunction "I5_7") (pintype "input"))
      (node (ref "IC14") (pin "8") (pinfunction "I6_8") (pintype "input"))
      (node (ref "IC14") (pin "9") (pinfunction "I7_9") (pintype "input"))
    )
    (net (code "92") (name "Net-(IC10A-O)") (class "Default")
      (node (ref "IC10") (pin "3") (pinfunction "O_3") (pintype "output"))
      (node (ref "IC10") (pin "5") (pinfunction "I1_5") (pintype "input"))
    )
    (net (code "93") (name "Net-(S1A-P)") (class "Default")
      (node (ref "R7") (pin "1") (pinfunction "1_1") (pintype "passive"))
      (node (ref "S1") (pin "13") (pinfunction "P_13") (pintype "passive"))
      (node (ref "S1") (pin "3") (pinfunction "O_3") (pintype "passive"))
    )
    (net (code "94") (name "PHI0") (class "Default")
      (node (ref "IC12") (pin "2") (pinfunction "I1_2") (pintype "input"))
      (node (ref "IC13") (pin "3") (pinfunction "I2_3") (pintype "input"))
      (node (ref "IC15") (pin "13") (pinfunction "O1_13") (pintype "output"))
      (node (ref "IC19") (pin "37") (pinfunction "PHI0_37") (pintype "input"))
    )
    (net (code "95") (name "ROM_SEL") (class "Default")
      (node (ref "IC13") (pin "9") (pinfunction "I8_9") (pintype "input"))
      (node (ref "R6") (pin "1") (pinfunction "1_1") (pintype "passive"))
      (node (ref "S1") (pin "9") (pinfunction "P_9") (pintype "passive"))
    )
    (net (code "96") (name "VCC") (class "Default")
      (node (ref "C1") (pin "1") (pinfunction "1_1") (pintype "passive"))
      (node (ref "C10") (pin "1") (pinfunction "1_1") (pintype "passive"))
      (node (ref "C11") (pin "1") (pinfunction "1_1") (pintype "passive"))
      (node (ref "C2") (pin "1") (pinfunction "1_1") (pintype "passive"))
      (node (ref "C3") (pin "1") (pinfunction "1_1") (pintype "passive"))
      (node (ref "C4") (pin "1") (pinfunction "1_1") (pintype "passive"))
      (node (ref "C5") (pin "1") (pinfunction "1_1") (pintype "passive"))
      (node (ref "C6") (pin "1") (pinfunction "1_1") (pintype "passive"))
      (node (ref "C7") (pin "1") (pinfunction "1_1") (pintype "passive"))
      (node (ref "C8") (pin "1") (pinfunction "1_1") (pintype "passive"))
      (node (ref "C9") (pin "1") (pinfunction "1_1") (pintype "passive"))
      (node (ref "IC1") (pin "11") (pinfunction "A1_11") (pintype "input"))
      (node (ref "IC1") (pin "13") (pinfunction "A2_13") (pintype "input"))
      (node (ref "IC1") (pin "15") (pinfunction "A3_15") (pintype "input"))
      (node (ref "IC1") (pin "17") (pinfunction "A4_17") (pintype "input"))
      (node (ref "IC1") (pin "2") (pinfunction "A1_2") (pintype "input"))
      (node (ref "IC1") (pin "4") (pinfunction "A2_4") (pintype "input"))
      (node (ref "IC1") (pin "6") (pinfunction "A3_6") (pintype "input"))
      (node (ref "IC1") (pin "8") (pinfunction "A4_8") (pintype "input"))
      (node (ref "IC14") (pin "4") (pinfunction "I2_4") (pintype "input"))
      (node (ref "IC14") (pin "6") (pinfunction "I4_6") (pintype "input"))
      (node (ref "IC18") (pin "28") (pinfunction "VCC_28") (pintype "power_in"))
      (node (ref "IC2") (pin "11") (pinfunction "A1_11") (pintype "input"))
      (node (ref "IC2") (pin "13") (pinfunction "A2_13") (pintype "input"))
      (node (ref "IC2") (pin "15") (pinfunction "A3_15") (pintype "input"))
      (node (ref "IC2") (pin "17") (pinfunction "A4_17") (pintype "input"))
      (node (ref "IC2") (pin "2") (pinfunction "A1_2") (pintype "input"))
      (node (ref "IC2") (pin "4") (pinfunction "A2_4") (pintype "input"))
      (node (ref "IC2") (pin "6") (pinfunction "A3_6") (pintype "input"))
      (node (ref "IC2") (pin "8") (pinfunction "A4_8") (pintype "input"))
      (node (ref "R1") (pin "2") (pinfunction "2_2") (pintype "passive"))
      (node (ref "R2") (pin "2") (pinfunction "2_2") (pintype "passive"))
      (node (ref "R3") (pin "2") (pinfunction "2_2") (pintype "passive"))
      (node (ref "R4") (pin "2") (pinfunction "2_2") (pintype "passive"))
      (node (ref "R5") (pin "2") (pinfunction "2_2") (pintype "passive"))
      (node (ref "R6") (pin "2") (pinfunction "2_2") (pintype "passive"))
      (node (ref "R7") (pin "2") (pinfunction "2_2") (pintype "passive"))
    )
    (net (code "97") (name "WEAK_HI") (class "Default")
      (node (ref "IC11") (pin "13") (pinfunction "A2_13") (pintype "input"))
      (node (ref "IC11") (pin "17") (pinfunction "A4_17") (pintype "input"))
      (node (ref "IC11") (pin "2") (pinfunction "A1_2") (pintype "input"))
      (node (ref "IC11") (pin "4") (pinfunction "A2_4") (pintype "input"))
      (node (ref "IC15") (pin "3") (pinfunction "I1_3") (pintype "input"))
      (node (ref "IC15") (pin "6") (pinfunction "I4_6") (pintype "input"))
      (node (ref "IC8") (pin "13") (pinfunction "5D_13") (pintype "input"))
      (node (ref "IC8") (pin "14") (pinfunction "6D_14") (pintype "input"))
      (node (ref "IC8") (pin "17") (pinfunction "7D_17") (pintype "input"))
      (node (ref "IC8") (pin "18") (pinfunction "8D_18") (pintype "input"))
      (node (ref "IC8") (pin "3") (pinfunction "1D_3") (pintype "input"))
      (node (ref "IC9") (pin "1") (pinfunction "CLR_1") (pintype "input"))
      (node (ref "IC9") (pin "10") (pinfunction "PRE_10") (pintype "input"))
      (node (ref "R1") (pin "1") (pinfunction "1_1") (pintype "passive"))
    )
    (net (code "98") (name "unconnected-(IC8A-1Q-Pad2)") (class "Default")
      (node (ref "IC8") (pin "2") (pinfunction "1Q_2") (pintype "tri_state"))
    )
    (net (code "99") (name "unconnected-(IC8A-5Q-Pad12)") (class "Default")
      (node (ref "IC8") (pin "12") (pinfunction "5Q_12") (pintype "tri_state"))
    )
    (net (code "100") (name "unconnected-(IC8A-6Q-Pad15)") (class "Default")
      (node (ref "IC8") (pin "15") (pinfunction "6Q_15") (pintype "tri_state"))
    )
    (net (code "101") (name "unconnected-(IC8A-7Q-Pad16)") (class "Default")
      (node (ref "IC8") (pin "16") (pinfunction "7Q_16") (pintype "tri_state"))
    )
    (net (code "102") (name "unconnected-(IC8A-8Q-Pad19)") (class "Default")
      (node (ref "IC8") (pin "19") (pinfunction "8Q_19") (pintype "tri_state"))
    )
    (net (code "103") (name "unconnected-(IC9A-~{Q}-Pad6)") (class "Default")
      (node (ref "IC9") (pin "6") (pinfunction "~{Q}_6") (pintype "output"))
    )
    (net (code "104") (name "unconnected-(IC9B-~{Q}-Pad8)") (class "Default")
      (node (ref "IC9") (pin "8") (pinfunction "~{Q}_8") (pintype "output"))
    )
    (net (code "105") (name "unconnected-(IC11A-Y1-Pad18)") (class "Default")
      (node (ref "IC11") (pin "18") (pinfunction "Y1_18") (pintype "tri_state"))
    )
    (net (code "106") (name "unconnected-(IC11A-Y2-Pad16)") (class "Default")
      (node (ref "IC11") (pin "16") (pinfunction "Y2_16") (pintype "tri_state"))
    )
    (net (code "107") (name "unconnected-(IC11B-Y2-Pad7)") (class "Default")
      (node (ref "IC11") (pin "7") (pinfunction "Y2_7") (pintype "tri_state"))
    )
    (net (code "108") (name "unconnected-(IC11B-Y4-Pad3)") (class "Default")
      (node (ref "IC11") (pin "3") (pinfunction "Y4_3") (pintype "tri_state"))
    )
    (net (code "109") (name "unconnected-(IC12A-O0-Pad12)") (class "Default")
      (node (ref "IC12") (pin "12") (pinfunction "O0_12") (pintype "output"))
    )
    (net (code "110") (name "unconnected-(IC12A-O1-Pad13)") (class "Default")
      (node (ref "IC12") (pin "13") (pinfunction "O1_13") (pintype "bidirectional"))
    )
    (net (code "111") (name "unconnected-(IC14A-O1-Pad13)") (class "Default")
      (node (ref "IC14") (pin "13") (pinfunction "O1_13") (pintype "bidirectional"))
    )
    (net (code "112") (name "unconnected-(IC14A-O2-Pad14)") (class "Default")
      (node (ref "IC14") (pin "14") (pinfunction "O2_14") (pintype "output"))
    )
    (net (code "113") (name "unconnected-(IC14A-O3-Pad15)") (class "Default")
      (node (ref "IC14") (pin "15") (pinfunction "O3_15") (pintype "output"))
    )
    (net (code "114") (name "unconnected-(IC14A-O4-Pad16)") (class "Default")
      (node (ref "IC14") (pin "16") (pinfunction "O4_16") (pintype "output"))
    )
    (net (code "115") (name "unconnected-(IC14A-O5-Pad17)") (class "Default")
      (node (ref "IC14") (pin "17") (pinfunction "O5_17") (pintype "output"))
    )
    (net (code "116") (name "unconnected-(IC15A-O2-Pad14)") (class "Default")
      (node (ref "IC15") (pin "14") (pinfunction "O2_14") (pintype "output"))
    )
    (net (code "117") (name "unconnected-(IC15A-O5-Pad17)") (class "Default")
      (node (ref "IC15") (pin "17") (pinfunction "O5_17") (pintype "output"))
    )
    (net (code "118") (name "unconnected-(IC18-VPP-Pad1)") (class "Default")
      (node (ref "IC18") (pin "1") (pinfunction "VPP_1") (pintype "input"))
    )
    (net (code "119") (name "unconnected-(IC19A-PHI1-Pad3)") (class "Default")
      (node (ref "IC19") (pin "3") (pinfunction "PHI1_3") (pintype "output"))
    )
    (net (code "120") (name "unconnected-(IC19A-PHI2-Pad39)") (class "Default")
      (node (ref "IC19") (pin "39") (pinfunction "PHI2_39") (pintype "output"))
    )
    (net (code "121") (name "unconnected-(IC19A-SYNC-Pad7)") (class "Default")
      (node (ref "IC19") (pin "7") (pinfunction "SYNC_7") (pintype "output"))
    )
    (net (code "122") (name "unconnected-(S1A-O-Pad1)") (class "Default")
      (node (ref "S1") (pin "1") (pinfunction "O_1") (pintype "passive"))
    )
    (net (code "123") (name "unconnected-(S1C-S-Pad10)") (class "Default")
      (node (ref "S1") (pin "10") (pinfunction "S_10") (pintype "passive"))
    )
    (net (code "124") (name "unconnected-(S1D-O-Pad7)") (class "Default")
      (node (ref "S1") (pin "7") (pinfunction "O_7") (pintype "passive"))
    )
    (net (code "125") (name "unconnected-(X1A-~{EXROM}-Pad9)") (class "Default")
      (node (ref "X1") (pin "9") (pinfunction "~{EXROM}_9") (pintype "input"))
    )
    (net (code "126") (name "unconnected-(X1A-~{GAME}-Pad8)") (class "Default")
      (node (ref "X1") (pin "8") (pinfunction "~{GAME}_8") (pintype "input"))
    )
    (net (code "127") (name "unconnected-(X1A-~{IO1}-Pad7)") (class "Default")
      (node (ref "X1") (pin "7") (pinfunction "~{IO1}_7") (pintype "output"))
    )
    (net (code "128") (name "unconnected-(X1A-~{IO2}-Pad10)") (class "Default")
      (node (ref "X1") (pin "10") (pinfunction "~{IO2}_10") (pintype "output"))
    )
    (net (code "129") (name "unconnected-(X1A-~{ROMH}-PadB)") (class "Default")
      (node (ref "X1") (pin "B") (pinfunction "~{ROMH}_B") (pintype "output"))
    )
    (net (code "130") (name "unconnected-(X1A-~{ROML}-Pad11)") (class "Default")
      (node (ref "X1") (pin "11") (pinfunction "~{ROML}_11") (pintype "output"))
    )
  )
)
